# mcu_debug.net
KiCad netlist of a schematic drawn in Altium Designer
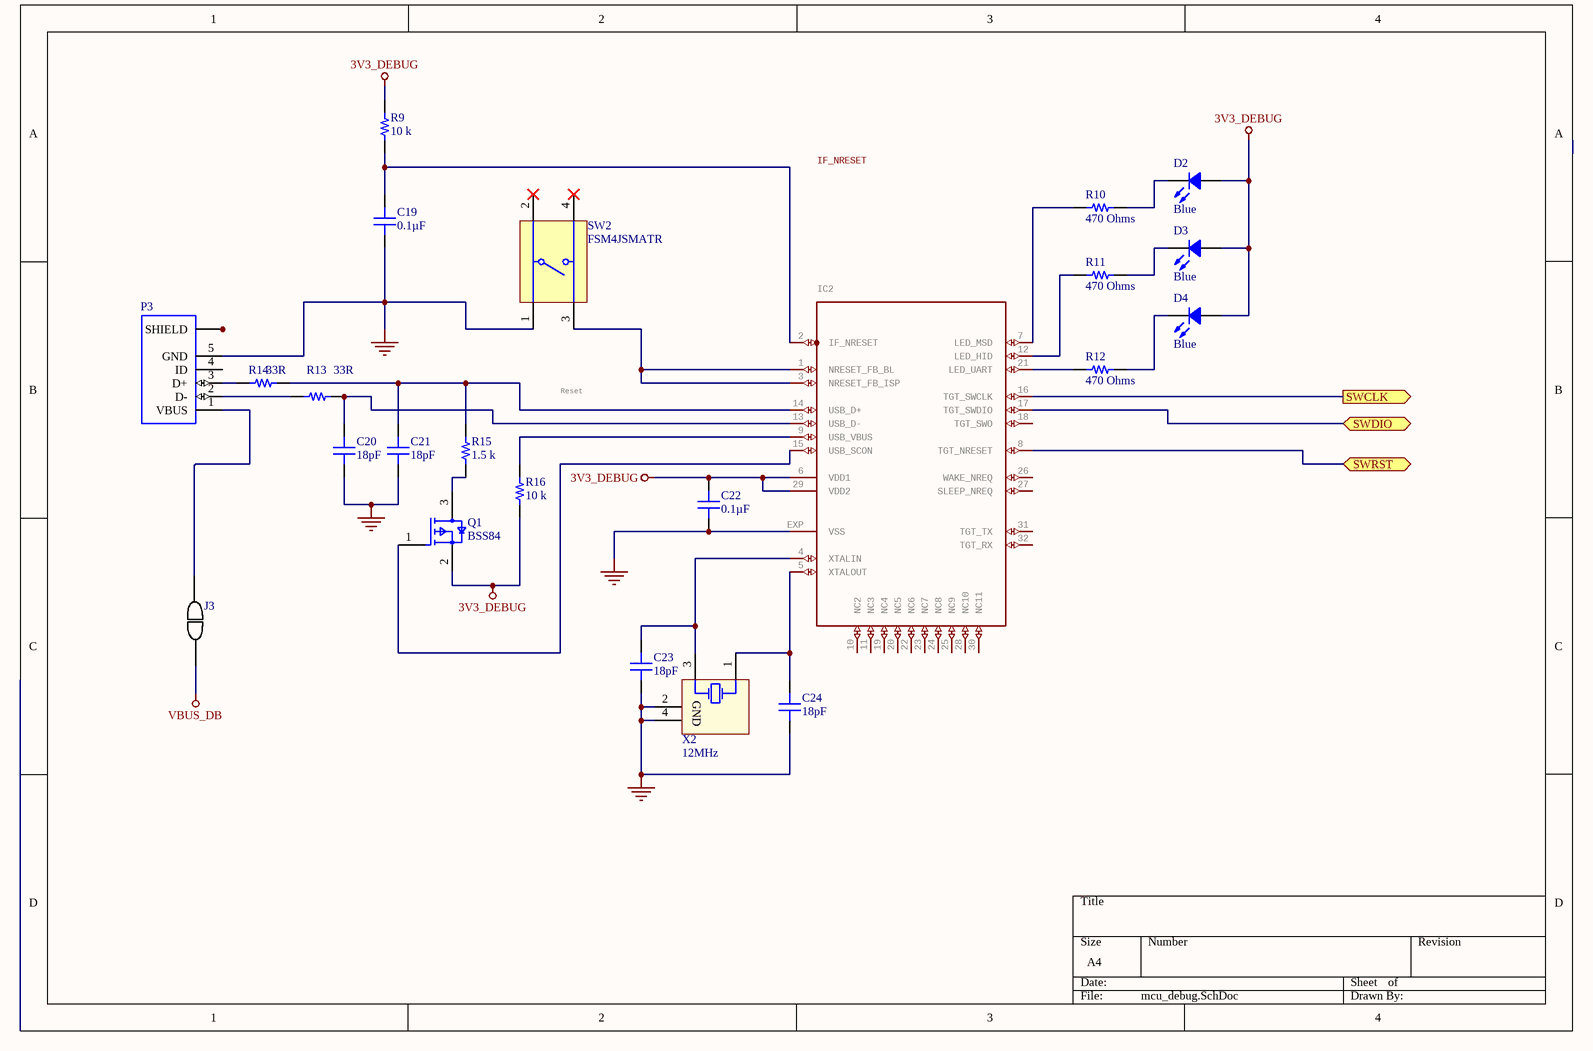
[diagram p0: mcu_debug.SchDoc]

(export (version "E")
  (design (tool "Eeschema 10.0.6"))
  (components
    (comp (ref "C19")
      (value "0.1µF")
      (footprint "CAP 0603_1608")
      (description "CAP CER 0.1UF 10V X7R 0603")
      (fields (field (name "PART NUMBER") "C0603T104K8RAC7867") (field (name "MANUFACTURER") "KEMET"))
      (libsource (lib "Celestial Altium Library - altium_library (2)") (part "Capacitor"))
    )
    (comp (ref "C20")
      (value "18pF")
      (footprint "CAP 0603_1608")
      (description "CAP CER 18PF 10V C0G/NP0 0603")
      (fields
        (field (name "PART NUMBER") "VJ0603A180FXQCW1BC")
        (field (name "MANUFACTURER") "Vishay Vitramon")
      )
      (libsource (lib "Celestial Altium Library - altium_library (2)") (part "Capacitor"))
    )
    (comp (ref "C21")
      (value "18pF")
      (footprint "CAP 0603_1608")
      (description "CAP CER 18PF 10V C0G/NP0 0603")
      (fields
        (field (name "PART NUMBER") "VJ0603A180FXQCW1BC")
        (field (name "MANUFACTURER") "Vishay Vitramon")
      )
      (libsource (lib "Celestial Altium Library - altium_library (2)") (part "Capacitor"))
    )
    (comp (ref "C22")
      (value "0.1µF")
      (footprint "CAP 0603_1608")
      (description "CAP CER 0.1UF 10V X7R 0603")
      (fields (field (name "PART NUMBER") "C0603T104K8RAC7867") (field (name "MANUFACTURER") "KEMET"))
      (libsource (lib "Celestial Altium Library - altium_library (2)") (part "Capacitor"))
    )
    (comp (ref "C23")
      (value "18pF")
      (footprint "CAP 0603_1608")
      (description "CAP CER 18PF 10V C0G/NP0 0603")
      (fields
        (field (name "PART NUMBER") "VJ0603A180FXQCW1BC")
        (field (name "MANUFACTURER") "Vishay Vitramon")
      )
      (libsource (lib "Celestial Altium Library - altium_library (2)") (part "Capacitor"))
    )
    (comp (ref "C24")
      (value "18pF")
      (footprint "CAP 0603_1608")
      (description "CAP CER 18PF 10V C0G/NP0 0603")
      (fields
        (field (name "PART NUMBER") "VJ0603A180FXQCW1BC")
        (field (name "MANUFACTURER") "Vishay Vitramon")
      )
      (libsource (lib "Celestial Altium Library - altium_library (2)") (part "Capacitor"))
    )
    (comp (ref "D2")
      (value "Blue")
      (footprint "LED 0603_1608 BLUE")
      (description "LED BLUE 0603 SMD")
      (fields
        (field (name "PART NUMBER") "VLMB1300-GS08")
        (field (name "MANUFACTURER") "Vishay Semiconductor Opto Division")
      )
      (libsource (lib "Celestial Altium Library - altium_library (2)") (part "LED"))
    )
    (comp (ref "D3")
      (value "Blue")
      (footprint "LED 0603_1608 BLUE")
      (description "LED BLUE 0603 SMD")
      (fields
        (field (name "PART NUMBER") "VLMB1300-GS08")
        (field (name "MANUFACTURER") "Vishay Semiconductor Opto Division")
      )
      (libsource (lib "Celestial Altium Library - altium_library (2)") (part "LED"))
    )
    (comp (ref "D4")
      (value "Blue")
      (footprint "LED 0603_1608 BLUE")
      (description "LED BLUE 0603 SMD")
      (fields
        (field (name "PART NUMBER") "VLMB1300-GS08")
        (field (name "MANUFACTURER") "Vishay Semiconductor Opto Division")
      )
      (libsource (lib "Celestial Altium Library - altium_library (2)") (part "LED"))
    )
    (comp (ref "IC2")
      (value "CMSIS-DAP Interface : 32-bit LPC11U00 ARM Cortex M3 RISC 64KB Flash 2.5V/3.3V 33-Pin HVQFN EP")
      (footprint "HVQFN33")
      (fields (field (name "MF") "NXP") (field (name "LIBRARYNAME") "mbed-HDK-MF-NXP"))
      (libsource (lib "mbed-HDK-MF-NXP") (part "IF_LPC11U35FHI33/501"))
    )
    (comp (ref "J3")
      (value "103185-2")
      (footprint "TE_103185-2")
      (description "02 MODII HDR SRST B/A .100CL")
      (libsource (lib "103185-2") (part "103185-2"))
    )
    (comp (ref "P3")
      (value "47346-0001")
      (footprint "MOLEX_47346-0001")
      (description "CONN RCPT 5POS MICRO USB R/A  SMD")
      (libsource (lib "47346-0001") (part "47346-0001"))
    )
    (comp (ref "Q1")
      (value "BSS84")
      (footprint "FP-SOT23-MFG")
      (description "MOSFET P-CH 50V 130MA SOT-23")
      (fields
        (field (name "OCTOPART") "https://octopart.com/bss84%2C215-nexperia-78739375")
        (field (name "MANUFACTURER PART NUMBER") "BSS84,215")
      )
      (libsource (lib "Altium Content Vault") (part "2a9bca3c979204b206c86ddeb8c1a69"))
    )
    (comp (ref "R9")
      (value "10 k")
      (footprint "RES 0603_1608")
      (description "RES 10K OHM 0.1% 1/16W 0603")
      (fields
        (field (name "PART NUMBER") "RNCS0603BKE10K0")
        (field (name "MANUFACTURER") "Stackpole Electronics Inc")
      )
      (libsource (lib "Celestial Altium Library - altium_library (2)") (part "Resistor"))
    )
    (comp (ref "R10")
      (value "470 Ohms")
      (footprint "RES 0603_1608")
      (description "RES SMD 470 OHM 5% 1/4W 0603")
      (fields (field (name "PART NUMBER") "CRCW0603470RJNEAHP") (field (name "MANUFACTURER") "Vishay Dale"))
      (libsource (lib "Celestial Altium Library - altium_library (2)") (part "Resistor"))
    )
    (comp (ref "R11")
      (value "470 Ohms")
      (footprint "RES 0603_1608")
      (description "RES SMD 470 OHM 5% 1/4W 0603")
      (fields (field (name "PART NUMBER") "CRCW0603470RJNEAHP") (field (name "MANUFACTURER") "Vishay Dale"))
      (libsource (lib "Celestial Altium Library - altium_library (2)") (part "Resistor"))
    )
    (comp (ref "R12")
      (value "470 Ohms")
      (footprint "RES 0603_1608")
      (description "RES SMD 470 OHM 5% 1/4W 0603")
      (fields (field (name "PART NUMBER") "CRCW0603470RJNEAHP") (field (name "MANUFACTURER") "Vishay Dale"))
      (libsource (lib "Celestial Altium Library - altium_library (2)") (part "Resistor"))
    )
    (comp (ref "R13")
      (value "33R")
      (footprint "RES 0603_1608")
      (description "RES SMD 33 OHM 0.1% 1/16W 0603")
      (fields
        (field (name "PART NUMBER") "CPF0603B33RE")
        (field (name "MANUFACTURER") "TE Connectivity Passive Product")
      )
      (libsource (lib "Celestial Altium Library - altium_library (2)") (part "Resistor"))
    )
    (comp (ref "R14")
      (value "33R")
      (footprint "RES 0603_1608")
      (description "RES SMD 33 OHM 0.1% 1/16W 0603")
      (fields
        (field (name "PART NUMBER") "CPF0603B33RE")
        (field (name "MANUFACTURER") "TE Connectivity Passive Product")
      )
      (libsource (lib "Celestial Altium Library - altium_library (2)") (part "Resistor"))
    )
    (comp (ref "R15")
      (value "1.5 k")
      (footprint "RES 0603_1608")
      (description "CRGP 0603 1K5 1%")
      (fields
        (field (name "PART NUMBER") "CRGP0603F1K5")
        (field (name "MANUFACTURER") "TE Connectivity Passive Product")
      )
      (libsource (lib "Celestial Altium Library - altium_library (2)") (part "Resistor"))
    )
    (comp (ref "R16")
      (value "10 k")
      (footprint "RES 0603_1608")
      (description "RES 10K OHM 0.1% 1/16W 0603")
      (fields
        (field (name "PART NUMBER") "RNCS0603BKE10K0")
        (field (name "MANUFACTURER") "Stackpole Electronics Inc")
      )
      (libsource (lib "Celestial Altium Library - altium_library (2)") (part "Resistor"))
    )
    (comp (ref "SW2")
      (value "FSM4JSMATR")
      (footprint "TECO-FSM4JSMATR_V")
      (description "Micro Miniature Push Button Switch FSM JSM, 50 mA, -35 to 85 degC, 4-Pin SMD, RoHS, Tape and Reel")
      (fields (field (name "MANUFACTURER") "TE Connectivity"))
      (libsource (lib "Altium Content Vault") (part "SW-SPST-4_A"))
    )
    (comp (ref "X2")
      (value "12MHz")
      (footprint "ABRA-ABMM2-4_V")
      (fields (field (name "MANUFACTURER") "Abracon") (field (name "PARTNUMBER") "ABMM2-8.000MHZ-E2-T"))
      (libsource (lib "Altium Content Vault") (part "ABRA-XTAL_1-3-4"))
    )
  )
  (nets
    (net (code "2") (name "/SWCLK") (class "Default")
      (node (ref "IC2") (pin "16") (pinfunction "TGT_SWCLK_16") (pintype "bidirectional"))
    )
    (net (code "3") (name "/SWDIO") (class "Default")
      (node (ref "IC2") (pin "17") (pinfunction "TGT_SWDIO_17") (pintype "bidirectional"))
    )
    (net (code "4") (name "/SWRST") (class "Default")
      (node (ref "IC2") (pin "8") (pinfunction "TGT_NRESET_8") (pintype "bidirectional"))
    )
    (net (code "5") (name "3V3_DEBUG") (class "Default")
      (node (ref "C22") (pin "2") (pinfunction "2_2") (pintype "passive"))
      (node (ref "D2") (pin "1") (pinfunction "1_1") (pintype "passive"))
      (node (ref "D3") (pin "1") (pinfunction "1_1") (pintype "passive"))
      (node (ref "D4") (pin "1") (pinfunction "1_1") (pintype "passive"))
      (node (ref "IC2") (pin "29") (pinfunction "VDD2_29") (pintype "power_in"))
      (node (ref "IC2") (pin "6") (pinfunction "VDD1_6") (pintype "power_in"))
      (node (ref "Q1") (pin "2") (pinfunction "S_2") (pintype "passive"))
      (node (ref "R16") (pin "1") (pinfunction "1_1") (pintype "passive"))
      (node (ref "R9") (pin "2") (pinfunction "2_2") (pintype "passive"))
    )
    (net (code "6") (name "GND") (class "Default")
      (node (ref "C19") (pin "1") (pinfunction "1_1") (pintype "passive"))
      (node (ref "C20") (pin "1") (pinfunction "1_1") (pintype "passive"))
      (node (ref "C21") (pin "1") (pinfunction "1_1") (pintype "passive"))
      (node (ref "C22") (pin "1") (pinfunction "1_1") (pintype "passive"))
      (node (ref "C23") (pin "1") (pinfunction "1_1") (pintype "passive"))
      (node (ref "C24") (pin "1") (pinfunction "1_1") (pintype "passive"))
      (node (ref "IC2") (pin "EXP") (pinfunction "VSS_EXP") (pintype "power_in"))
      (node (ref "P3") (pin "5") (pinfunction "GND_5") (pintype "power_in"))
      (node (ref "SW2") (pin "1") (pinfunction "1_1") (pintype "passive"))
      (node (ref "X2") (pin "2") (pinfunction "GND_2") (pintype "power_in"))
      (node (ref "X2") (pin "4") (pinfunction "GND_4") (pintype "power_in"))
    )
    (net (code "7") (name "Net-(D2-Pad2)") (class "Default")
      (node (ref "D2") (pin "2") (pinfunction "2_2") (pintype "passive"))
      (node (ref "R10") (pin "2") (pinfunction "2_2") (pintype "passive"))
    )
    (net (code "8") (name "Net-(D3-Pad2)") (class "Default")
      (node (ref "D3") (pin "2") (pinfunction "2_2") (pintype "passive"))
      (node (ref "R11") (pin "2") (pinfunction "2_2") (pintype "passive"))
    )
    (net (code "9") (name "Net-(D4-Pad2)") (class "Default")
      (node (ref "D4") (pin "2") (pinfunction "2_2") (pintype "passive"))
      (node (ref "R12") (pin "2") (pinfunction "2_2") (pintype "passive"))
    )
    (net (code "10") (name "Net-(IC2-IF_NRESET)") (class "Default")
      (node (ref "C19") (pin "2") (pinfunction "2_2") (pintype "passive"))
      (node (ref "IC2") (pin "2") (pinfunction "IF_NRESET_2") (pintype "bidirectional"))
      (node (ref "R9") (pin "1") (pinfunction "1_1") (pintype "passive"))
    )
    (net (code "11") (name "Net-(IC2-LED_HID)") (class "Default")
      (node (ref "IC2") (pin "12") (pinfunction "LED_HID_12") (pintype "bidirectional"))
      (node (ref "R11") (pin "1") (pinfunction "1_1") (pintype "passive"))
    )
    (net (code "12") (name "Net-(IC2-LED_MSD)") (class "Default")
      (node (ref "IC2") (pin "7") (pinfunction "LED_MSD_7") (pintype "bidirectional"))
      (node (ref "R10") (pin "1") (pinfunction "1_1") (pintype "passive"))
    )
    (net (code "13") (name "Net-(IC2-LED_UART)") (class "Default")
      (node (ref "IC2") (pin "21") (pinfunction "LED_UART_21") (pintype "bidirectional"))
      (node (ref "R12") (pin "1") (pinfunction "1_1") (pintype "passive"))
    )
    (net (code "14") (name "Net-(IC2-NRESET_FB_BL)") (class "Default")
      (node (ref "IC2") (pin "1") (pinfunction "NRESET_FB_BL_1") (pintype "bidirectional"))
      (node (ref "IC2") (pin "3") (pinfunction "NRESET_FB_ISP_3") (pintype "bidirectional"))
      (node (ref "SW2") (pin "3") (pinfunction "3_3") (pintype "passive"))
    )
    (net (code "15") (name "Net-(IC2-USB_D+)") (class "Default")
      (node (ref "C21") (pin "2") (pinfunction "2_2") (pintype "passive"))
      (node (ref "IC2") (pin "14") (pinfunction "USB_D+_14") (pintype "bidirectional"))
      (node (ref "R14") (pin "2") (pinfunction "2_2") (pintype "passive"))
      (node (ref "R15") (pin "2") (pinfunction "2_2") (pintype "passive"))
    )
    (net (code "16") (name "Net-(IC2-USB_D-)") (class "Default")
      (node (ref "C20") (pin "2") (pinfunction "2_2") (pintype "passive"))
      (node (ref "IC2") (pin "13") (pinfunction "USB_D-_13") (pintype "bidirectional"))
      (node (ref "R13") (pin "2") (pinfunction "2_2") (pintype "passive"))
    )
    (net (code "17") (name "Net-(IC2-USB_SCON)") (class "Default")
      (node (ref "IC2") (pin "15") (pinfunction "USB_SCON_15") (pintype "bidirectional"))
      (node (ref "Q1") (pin "1") (pinfunction "G_1") (pintype "passive"))
    )
    (net (code "18") (name "Net-(IC2-USB_VBUS)") (class "Default")
      (node (ref "IC2") (pin "9") (pinfunction "USB_VBUS_9") (pintype "bidirectional"))
      (node (ref "R16") (pin "2") (pinfunction "2_2") (pintype "passive"))
    )
    (net (code "19") (name "Net-(IC2-XTALIN)") (class "Default")
      (node (ref "C23") (pin "2") (pinfunction "2_2") (pintype "passive"))
      (node (ref "IC2") (pin "4") (pinfunction "XTALIN_4") (pintype "bidirectional"))
      (node (ref "X2") (pin "3") (pinfunction "X2_3") (pintype "passive"))
    )
    (net (code "20") (name "Net-(IC2-XTALOUT)") (class "Default")
      (node (ref "C24") (pin "2") (pinfunction "2_2") (pintype "passive"))
      (node (ref "IC2") (pin "5") (pinfunction "XTALOUT_5") (pintype "bidirectional"))
      (node (ref "X2") (pin "1") (pinfunction "X1_1") (pintype "passive"))
    )
    (net (code "21") (name "Net-(P3-D+)") (class "Default")
      (node (ref "P3") (pin "3") (pinfunction "D+_3") (pintype "bidirectional"))
      (node (ref "R14") (pin "1") (pinfunction "1_1") (pintype "passive"))
    )
    (net (code "22") (name "Net-(P3-D-)") (class "Default")
      (node (ref "P3") (pin "2") (pinfunction "D-_2") (pintype "bidirectional"))
      (node (ref "R13") (pin "1") (pinfunction "1_1") (pintype "passive"))
    )
    (net (code "23") (name "Net-(P3-SHIELD-PadSH1)") (class "Default")
      (node (ref "P3") (pin "SH1") (pinfunction "SHIELD_SH1") (pintype "passive"))
      (node (ref "P3") (pin "SH2") (pinfunction "SHIELD_SH2") (pintype "passive"))
      (node (ref "P3") (pin "SH3") (pinfunction "SHIELD_SH3") (pintype "passive"))
      (node (ref "P3") (pin "SH4") (pinfunction "SHIELD_SH4") (pintype "passive"))
      (node (ref "P3") (pin "SH5") (pinfunction "SHIELD_SH5") (pintype "passive"))
      (node (ref "P3") (pin "SH6") (pinfunction "SHIELD_SH6") (pintype "passive"))
    )
    (net (code "24") (name "Net-(P3-VBUS)") (class "Default")
      (node (ref "J3") (pin "2") (pinfunction "2_2") (pintype "passive"))
      (node (ref "P3") (pin "1") (pinfunction "VBUS_1") (pintype "power_in"))
    )
    (net (code "25") (name "Net-(Q1-D)") (class "Default")
      (node (ref "Q1") (pin "3") (pinfunction "D_3") (pintype "passive"))
      (node (ref "R15") (pin "1") (pinfunction "1_1") (pintype "passive"))
    )
    (net (code "26") (name "VBUS_DB") (class "Default")
      (node (ref "J3") (pin "1") (pinfunction "1_1") (pintype "passive"))
    )
    (net (code "27") (name "unconnected-(IC2-NC2-Pad10)") (class "Default")
      (node (ref "IC2") (pin "10") (pinfunction "NC2_10") (pintype "bidirectional"))
    )
    (net (code "28") (name "unconnected-(IC2-NC3-Pad11)") (class "Default")
      (node (ref "IC2") (pin "11") (pinfunction "NC3_11") (pintype "bidirectional"))
    )
    (net (code "29") (name "unconnected-(IC2-NC4-Pad19)") (class "Default")
      (node (ref "IC2") (pin "19") (pinfunction "NC4_19") (pintype "bidirectional"))
    )
    (net (code "30") (name "unconnected-(IC2-NC5-Pad20)") (class "Default")
      (node (ref "IC2") (pin "20") (pinfunction "NC5_20") (pintype "bidirectional"))
    )
    (net (code "31") (name "unconnected-(IC2-NC6-Pad22)") (class "Default")
      (node (ref "IC2") (pin "22") (pinfunction "NC6_22") (pintype "bidirectional"))
    )
    (net (code "32") (name "unconnected-(IC2-NC7-Pad23)") (class "Default")
      (node (ref "IC2") (pin "23") (pinfunction "NC7_23") (pintype "bidirectional"))
    )
    (net (code "33") (name "unconnected-(IC2-NC8-Pad24)") (class "Default")
      (node (ref "IC2") (pin "24") (pinfunction "NC8_24") (pintype "bidirectional"))
    )
    (net (code "34") (name "unconnected-(IC2-NC9-Pad25)") (class "Default")
      (node (ref "IC2") (pin "25") (pinfunction "NC9_25") (pintype "bidirectional"))
    )
    (net (code "35") (name "unconnected-(IC2-NC10-Pad28)") (class "Default")
      (node (ref "IC2") (pin "28") (pinfunction "NC10_28") (pintype "bidirectional"))
    )
    (net (code "36") (name "unconnected-(IC2-NC11-Pad30)") (class "Default")
      (node (ref "IC2") (pin "30") (pinfunction "NC11_30") (pintype "bidirectional"))
    )
    (net (code "37") (name "unconnected-(IC2-SLEEP_NREQ-Pad27)") (class "Default")
      (node (ref "IC2") (pin "27") (pinfunction "SLEEP_NREQ_27") (pintype "bidirectional"))
    )
    (net (code "38") (name "unconnected-(IC2-TGT_RX-Pad32)") (class "Default")
      (node (ref "IC2") (pin "32") (pinfunction "TGT_RX_32") (pintype "bidirectional"))
    )
    (net (code "39") (name "unconnected-(IC2-TGT_SWO-Pad18)") (class "Default")
      (node (ref "IC2") (pin "18") (pinfunction "TGT_SWO_18") (pintype "bidirectional"))
    )
    (net (code "40") (name "unconnected-(IC2-TGT_TX-Pad31)") (class "Default")
      (node (ref "IC2") (pin "31") (pinfunction "TGT_TX_31") (pintype "bidirectional"))
    )
    (net (code "41") (name "unconnected-(IC2-WAKE_NREQ-Pad26)") (class "Default")
      (node (ref "IC2") (pin "26") (pinfunction "WAKE_NREQ_26") (pintype "bidirectional"))
    )
    (net (code "42") (name "unconnected-(P3-ID-Pad4)") (class "Default")
      (node (ref "P3") (pin "4") (pinfunction "ID_4") (pintype "passive"))
    )
    (net (code "43") (name "unconnected-(SW2-Pad2)") (class "Default")
      (node (ref "SW2") (pin "2") (pinfunction "2_2") (pintype "passive+no_connect"))
    )
    (net (code "44") (name "unconnected-(SW2-Pad4)") (class "Default")
      (node (ref "SW2") (pin "4") (pinfunction "4_4") (pintype "passive+no_connect"))
    )
  )
)
